# DicioBkUP.net
KiCad netlist of a schematic drawn in EAGLE
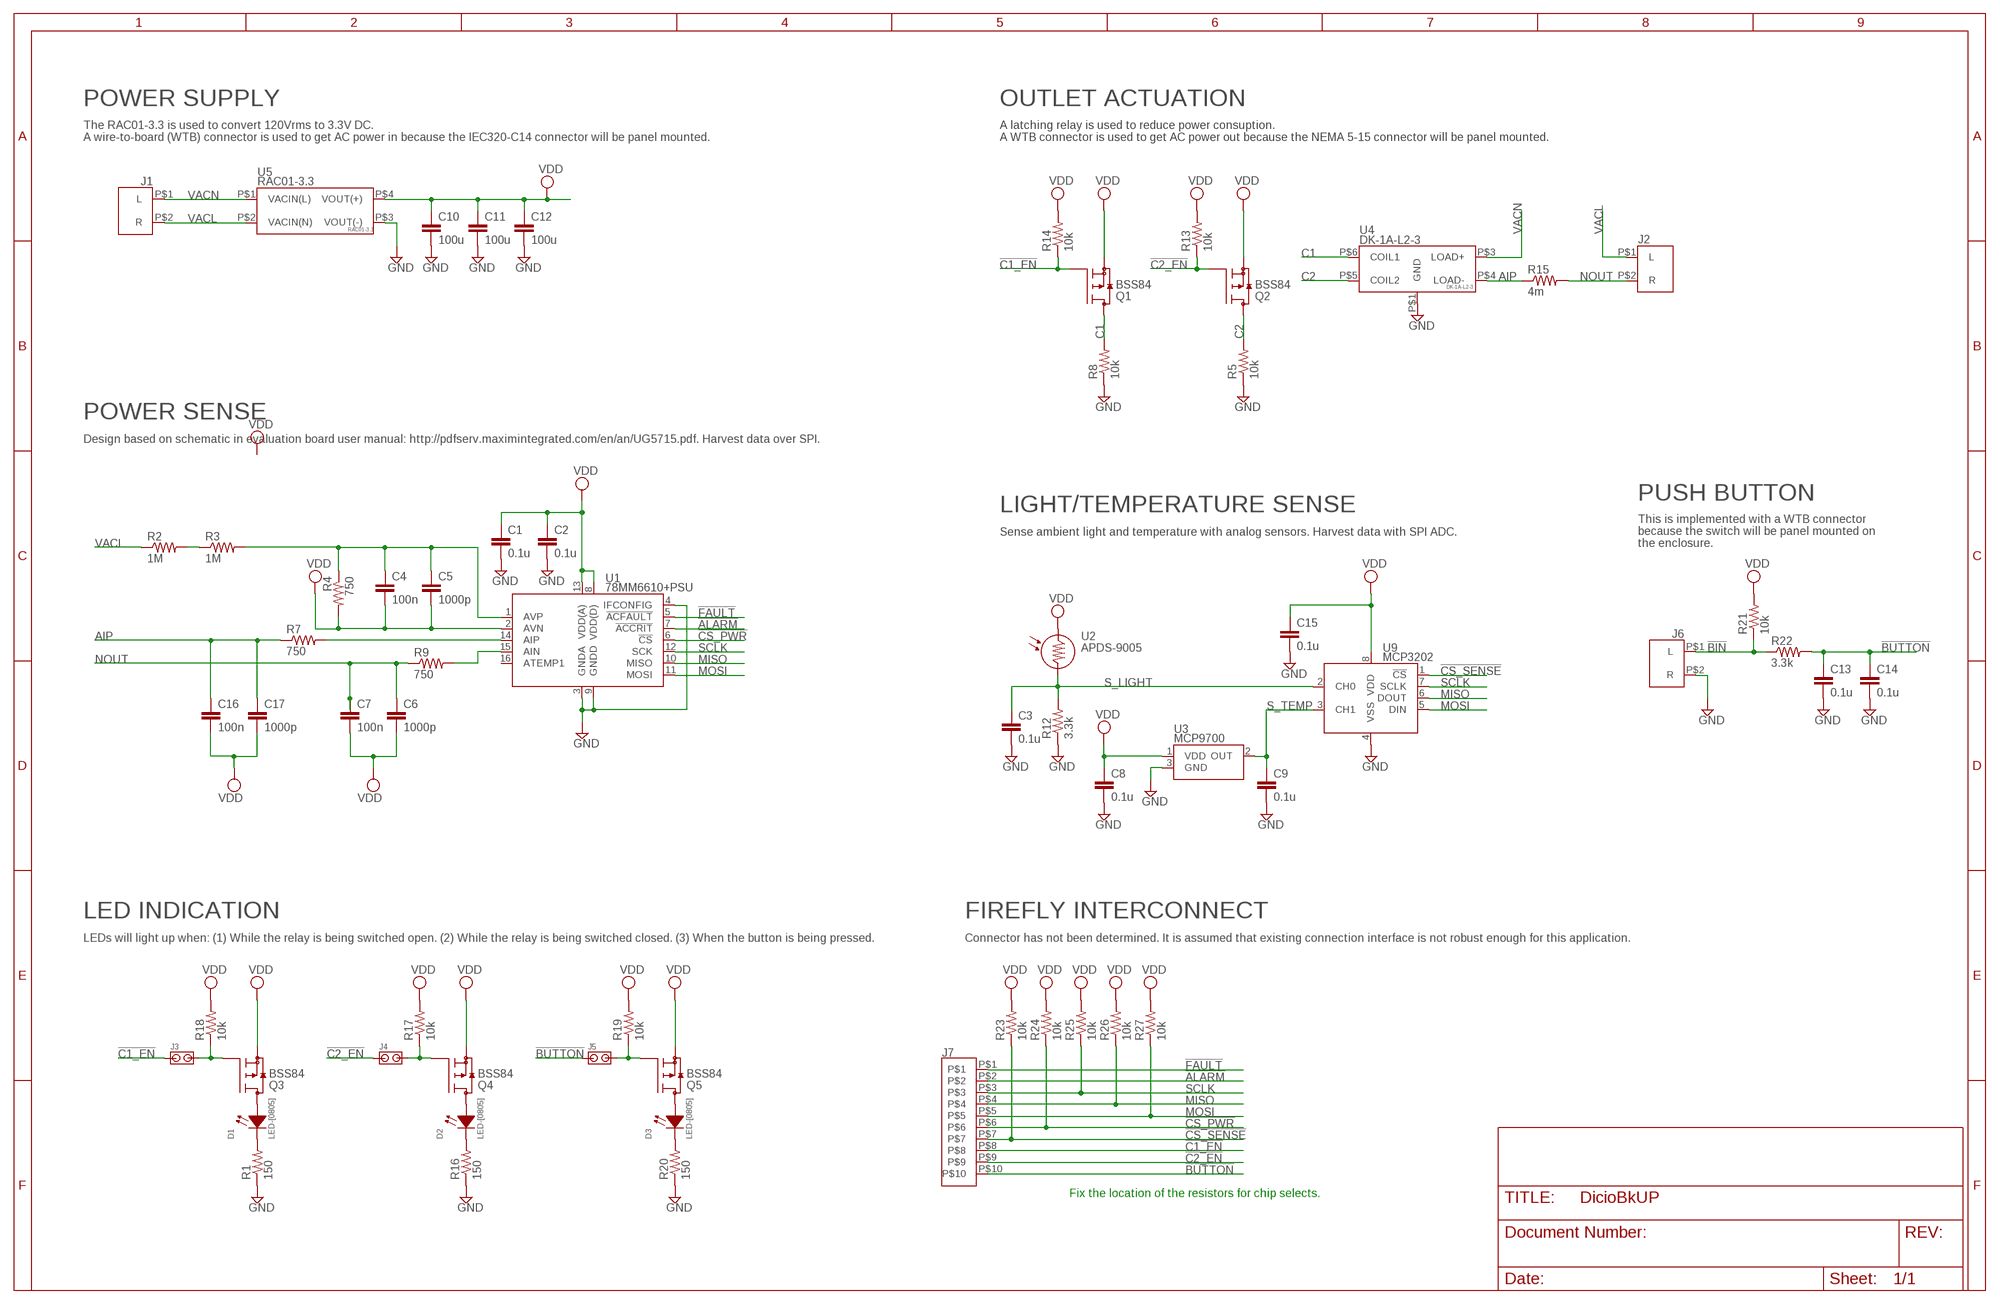
[diagram p0: schematic, sheet 1]

(export (version "E")
  (design (tool "Eeschema 10.0.6"))
  (components
    (comp (ref "C1")
      (value "0.1u")
      (footprint "eagle-import:C0805")
      (libsource (lib "eagle-import") (part "C-EUC0805"))
    )
    (comp (ref "C2")
      (value "0.1u")
      (footprint "eagle-import:C0805")
      (libsource (lib "eagle-import") (part "C-EUC0805"))
    )
    (comp (ref "C3")
      (value "0.1u")
      (footprint "eagle-import:C0805")
      (libsource (lib "eagle-import") (part "C-EUC0805"))
    )
    (comp (ref "C4")
      (value "100n")
      (footprint "eagle-import:C0805")
      (libsource (lib "eagle-import") (part "C-EUC0805"))
    )
    (comp (ref "C5")
      (value "1000p")
      (footprint "eagle-import:C0805")
      (libsource (lib "eagle-import") (part "C-EUC0805"))
    )
    (comp (ref "C6")
      (value "1000p")
      (footprint "eagle-import:C0805")
      (libsource (lib "eagle-import") (part "C-EUC0805"))
    )
    (comp (ref "C7")
      (value "100n")
      (footprint "eagle-import:C0805")
      (libsource (lib "eagle-import") (part "C-EUC0805"))
    )
    (comp (ref "C8")
      (value "0.1u")
      (footprint "eagle-import:C0805")
      (libsource (lib "eagle-import") (part "C-EUC0805"))
    )
    (comp (ref "C9")
      (value "0.1u")
      (footprint "eagle-import:C0805")
      (libsource (lib "eagle-import") (part "C-EUC0805"))
    )
    (comp (ref "C10")
      (value "100u")
      (footprint "eagle-import:C1206")
      (libsource (lib "eagle-import") (part "C-EUC1206"))
    )
    (comp (ref "C11")
      (value "100u")
      (footprint "eagle-import:C1206")
      (libsource (lib "eagle-import") (part "C-EUC1206"))
    )
    (comp (ref "C12")
      (value "100u")
      (footprint "eagle-import:C1206")
      (libsource (lib "eagle-import") (part "C-EUC1206"))
    )
    (comp (ref "C13")
      (value "0.1u")
      (footprint "eagle-import:C0805")
      (libsource (lib "eagle-import") (part "C-EUC0805"))
    )
    (comp (ref "C14")
      (value "0.1u")
      (footprint "eagle-import:C0805")
      (libsource (lib "eagle-import") (part "C-EUC0805"))
    )
    (comp (ref "C15")
      (value "0.1u")
      (footprint "eagle-import:C0805")
      (libsource (lib "eagle-import") (part "C-EUC0805"))
    )
    (comp (ref "C16")
      (value "100n")
      (footprint "eagle-import:C0805")
      (libsource (lib "eagle-import") (part "C-EUC0805"))
    )
    (comp (ref "C17")
      (value "1000p")
      (footprint "eagle-import:C0805")
      (libsource (lib "eagle-import") (part "C-EUC0805"))
    )
    (comp (ref "D1")
      (value "LED-[0805]")
      (footprint "eagle-import:L0805")
      (libsource (lib "eagle-import") (part "LED-[0805]"))
    )
    (comp (ref "D2")
      (value "LED-[0805]")
      (footprint "eagle-import:L0805")
      (libsource (lib "eagle-import") (part "LED-[0805]"))
    )
    (comp (ref "D3")
      (value "LED-[0805]")
      (footprint "eagle-import:L0805")
      (libsource (lib "eagle-import") (part "LED-[0805]"))
    )
    (comp (ref "J1")
      (value "WTB-2")
      (footprint "eagle-import:[TERM][2][0.2]")
      (libsource (lib "eagle-import") (part "WTB-2"))
    )
    (comp (ref "J2")
      (value "WTB-2")
      (footprint "eagle-import:[TERM][2][0.2]")
      (libsource (lib "eagle-import") (part "WTB-2"))
    )
    (comp (ref "J3")
      (value "JMP2")
      (footprint "eagle-import:JMP2")
      (libsource (lib "eagle-import") (part "JMP2"))
    )
    (comp (ref "J4")
      (value "JMP2")
      (footprint "eagle-import:JMP2")
      (libsource (lib "eagle-import") (part "JMP2"))
    )
    (comp (ref "J5")
      (value "JMP2")
      (footprint "eagle-import:JMP2")
      (libsource (lib "eagle-import") (part "JMP2"))
    )
    (comp (ref "J6")
      (value "WTB-2")
      (footprint "eagle-import:[TERM][2][0.2]")
      (libsource (lib "eagle-import") (part "WTB-2"))
    )
    (comp (ref "J7")
      (value "TERM10")
      (footprint "eagle-import:TERM10")
      (libsource (lib "eagle-import") (part "TERM10"))
    )
    (comp (ref "Q1")
      (value "BSS84")
      (footprint "eagle-import:SOT23")
      (libsource (lib "eagle-import") (part "BSS84"))
    )
    (comp (ref "Q2")
      (value "BSS84")
      (footprint "eagle-import:SOT23")
      (libsource (lib "eagle-import") (part "BSS84"))
    )
    (comp (ref "Q3")
      (value "BSS84")
      (footprint "eagle-import:SOT23")
      (libsource (lib "eagle-import") (part "BSS84"))
    )
    (comp (ref "Q4")
      (value "BSS84")
      (footprint "eagle-import:SOT23")
      (libsource (lib "eagle-import") (part "BSS84"))
    )
    (comp (ref "Q5")
      (value "BSS84")
      (footprint "eagle-import:SOT23")
      (libsource (lib "eagle-import") (part "BSS84"))
    )
    (comp (ref "R1")
      (value "150")
      (footprint "eagle-import:R0805")
      (libsource (lib "eagle-import") (part "R-US_R0805"))
    )
    (comp (ref "R2")
      (value "1M")
      (footprint "eagle-import:R0805")
      (libsource (lib "eagle-import") (part "R-US_R0805"))
    )
    (comp (ref "R3")
      (value "1M")
      (footprint "eagle-import:R0805")
      (libsource (lib "eagle-import") (part "R-US_R0805"))
    )
    (comp (ref "R4")
      (value "750")
      (footprint "eagle-import:R0805")
      (libsource (lib "eagle-import") (part "R-US_R0805"))
    )
    (comp (ref "R5")
      (value "10k")
      (footprint "eagle-import:R0805")
      (libsource (lib "eagle-import") (part "R-US_R0805"))
    )
    (comp (ref "R7")
      (value "750")
      (footprint "eagle-import:R0805")
      (libsource (lib "eagle-import") (part "R-US_R0805"))
    )
    (comp (ref "R8")
      (value "10k")
      (footprint "eagle-import:R0805")
      (libsource (lib "eagle-import") (part "R-US_R0805"))
    )
    (comp (ref "R9")
      (value "750")
      (footprint "eagle-import:R0805")
      (libsource (lib "eagle-import") (part "R-US_R0805"))
    )
    (comp (ref "R12")
      (value "3.3k")
      (footprint "eagle-import:R0805")
      (libsource (lib "eagle-import") (part "R-US_R0805"))
    )
    (comp (ref "R13")
      (value "10k")
      (footprint "eagle-import:R0805")
      (libsource (lib "eagle-import") (part "R-US_R0805"))
    )
    (comp (ref "R14")
      (value "10k")
      (footprint "eagle-import:R0805")
      (libsource (lib "eagle-import") (part "R-US_R0805"))
    )
    (comp (ref "R15")
      (value "4m")
      (footprint "eagle-import:R2512")
      (libsource (lib "eagle-import") (part "R-US_R2512"))
    )
    (comp (ref "R16")
      (value "150")
      (footprint "eagle-import:R0805")
      (libsource (lib "eagle-import") (part "R-US_R0805"))
    )
    (comp (ref "R17")
      (value "10k")
      (footprint "eagle-import:R0805")
      (libsource (lib "eagle-import") (part "R-US_R0805"))
    )
    (comp (ref "R18")
      (value "10k")
      (footprint "eagle-import:R0805")
      (libsource (lib "eagle-import") (part "R-US_R0805"))
    )
    (comp (ref "R19")
      (value "10k")
      (footprint "eagle-import:R0805")
      (libsource (lib "eagle-import") (part "R-US_R0805"))
    )
    (comp (ref "R20")
      (value "150")
      (footprint "eagle-import:R0805")
      (libsource (lib "eagle-import") (part "R-US_R0805"))
    )
    (comp (ref "R21")
      (value "10k")
      (footprint "eagle-import:R0805")
      (libsource (lib "eagle-import") (part "R-US_R0805"))
    )
    (comp (ref "R22")
      (value "3.3k")
      (footprint "eagle-import:R0805")
      (libsource (lib "eagle-import") (part "R-US_R0805"))
    )
    (comp (ref "R23")
      (value "10k")
      (footprint "eagle-import:R0805")
      (libsource (lib "eagle-import") (part "R-US_R0805"))
    )
    (comp (ref "R24")
      (value "10k")
      (footprint "eagle-import:R0805")
      (libsource (lib "eagle-import") (part "R-US_R0805"))
    )
    (comp (ref "R25")
      (value "10k")
      (footprint "eagle-import:R0805")
      (libsource (lib "eagle-import") (part "R-US_R0805"))
    )
    (comp (ref "R26")
      (value "10k")
      (footprint "eagle-import:R0805")
      (libsource (lib "eagle-import") (part "R-US_R0805"))
    )
    (comp (ref "R27")
      (value "10k")
      (footprint "eagle-import:R0805")
      (libsource (lib "eagle-import") (part "R-US_R0805"))
    )
    (comp (ref "U1")
      (value "78MM6610+PSU")
      (footprint "eagle-import:TSSOP16")
      (libsource (lib "eagle-import") (part "78MM6610+PSU"))
    )
    (comp (ref "U2")
      (value "APDS-9005")
      (footprint "eagle-import:APDS-9005")
      (libsource (lib "eagle-import") (part "APDS-9005"))
    )
    (comp (ref "U3")
      (value "MCP9700")
      (footprint "eagle-import:SOT23")
      (libsource (lib "eagle-import") (part "MCP9700"))
    )
    (comp (ref "U4")
      (value "DK-1A-L2-3")
      (footprint "eagle-import:DK-1A-L2-3")
      (libsource (lib "eagle-import") (part "DK-1A-L2-3"))
    )
    (comp (ref "U5")
      (value "RAC01-3.3")
      (footprint "eagle-import:RAC01-3.3")
      (libsource (lib "eagle-import") (part "RAC01-3.3"))
    )
    (comp (ref "U9")
      (value "MCP3202")
      (footprint "eagle-import:MSOP-8[MCP3202]")
      (libsource (lib "eagle-import") (part "MCP3202"))
    )
  )
  (nets
    (net (code "1") (name "/AIP") (class "Default")
      (node (ref "C16") (pin "1") (pinfunction "1_1") (pintype "passive"))
      (node (ref "C17") (pin "1") (pinfunction "1_1") (pintype "passive"))
      (node (ref "R15") (pin "1") (pinfunction "1_1") (pintype "passive"))
      (node (ref "R7") (pin "1") (pinfunction "1_1") (pintype "passive"))
      (node (ref "U4") (pin "P$4") (pinfunction "LOAD-_P$4") (pintype "bidirectional"))
    )
    (net (code "2") (name "/C1") (class "Default")
      (node (ref "Q1") (pin "3") (pinfunction "D_3") (pintype "bidirectional"))
      (node (ref "R8") (pin "2") (pinfunction "2_2") (pintype "passive"))
      (node (ref "U4") (pin "P$6") (pinfunction "COIL1_P$6") (pintype "bidirectional"))
    )
    (net (code "3") (name "/C2") (class "Default")
      (node (ref "Q2") (pin "3") (pinfunction "D_3") (pintype "bidirectional"))
      (node (ref "R5") (pin "2") (pinfunction "2_2") (pintype "passive"))
      (node (ref "U4") (pin "P$5") (pinfunction "COIL2_P$5") (pintype "bidirectional"))
    )
    (net (code "4") (name "/MISO") (class "Default")
      (node (ref "J7") (pin "P$4") (pinfunction "P$4_P$4") (pintype "bidirectional"))
      (node (ref "R26") (pin "1") (pinfunction "1_1") (pintype "passive"))
      (node (ref "U1") (pin "10") (pinfunction "MISO_10") (pintype "bidirectional"))
      (node (ref "U9") (pin "6") (pinfunction "DOUT_6") (pintype "bidirectional"))
    )
    (net (code "5") (name "/MOSI") (class "Default")
      (node (ref "J7") (pin "P$5") (pinfunction "P$5_P$5") (pintype "bidirectional"))
      (node (ref "R27") (pin "1") (pinfunction "1_1") (pintype "passive"))
      (node (ref "U1") (pin "11") (pinfunction "MOSI_11") (pintype "bidirectional"))
      (node (ref "U9") (pin "5") (pinfunction "DIN_5") (pintype "bidirectional"))
    )
    (net (code "6") (name "/NOUT") (class "Default")
      (node (ref "C6") (pin "1") (pinfunction "1_1") (pintype "passive"))
      (node (ref "C7") (pin "1") (pinfunction "1_1") (pintype "passive"))
      (node (ref "J2") (pin "P$2") (pinfunction "R_P$2") (pintype "bidirectional"))
      (node (ref "R15") (pin "2") (pinfunction "2_2") (pintype "passive"))
      (node (ref "R9") (pin "1") (pinfunction "1_1") (pintype "passive"))
    )
    (net (code "7") (name "/SCLK") (class "Default")
      (node (ref "J7") (pin "P$3") (pinfunction "P$3_P$3") (pintype "bidirectional"))
      (node (ref "R25") (pin "1") (pinfunction "1_1") (pintype "passive"))
      (node (ref "U1") (pin "12") (pinfunction "SCK_12") (pintype "bidirectional"))
      (node (ref "U9") (pin "7") (pinfunction "SCLK_7") (pintype "bidirectional"))
    )
    (net (code "8") (name "/S_LIGHT") (class "Default")
      (node (ref "C3") (pin "1") (pinfunction "1_1") (pintype "passive"))
      (node (ref "R12") (pin "2") (pinfunction "2_2") (pintype "passive"))
      (node (ref "U2") (pin "6") (pinfunction "ROUT_6") (pintype "bidirectional"))
      (node (ref "U9") (pin "2") (pinfunction "CH0_2") (pintype "bidirectional"))
    )
    (net (code "9") (name "/S_TEMP") (class "Default")
      (node (ref "C9") (pin "1") (pinfunction "1_1") (pintype "passive"))
      (node (ref "U3") (pin "2") (pinfunction "OUT_2") (pintype "bidirectional"))
      (node (ref "U9") (pin "3") (pinfunction "CH1_3") (pintype "bidirectional"))
    )
    (net (code "10") (name "/VACL") (class "Default")
      (node (ref "J1") (pin "P$2") (pinfunction "R_P$2") (pintype "bidirectional"))
      (node (ref "J2") (pin "P$1") (pinfunction "L_P$1") (pintype "bidirectional"))
      (node (ref "R2") (pin "1") (pinfunction "1_1") (pintype "passive"))
      (node (ref "U5") (pin "P$2") (pinfunction "VACIN(N)_P$2") (pintype "bidirectional"))
    )
    (net (code "11") (name "/VACN") (class "Default")
      (node (ref "J1") (pin "P$1") (pinfunction "L_P$1") (pintype "bidirectional"))
      (node (ref "U4") (pin "P$3") (pinfunction "LOAD+_P$3") (pintype "bidirectional"))
      (node (ref "U5") (pin "P$1") (pinfunction "VACIN(L)_P$1") (pintype "bidirectional"))
    )
    (net (code "12") (name "/~{ALARM}") (class "Default")
      (node (ref "J7") (pin "P$2") (pinfunction "P$2_P$2") (pintype "bidirectional"))
      (node (ref "U1") (pin "7") (pinfunction "~{ACCRIT}_7") (pintype "bidirectional"))
    )
    (net (code "13") (name "/~{BIN}") (class "Default")
      (node (ref "J6") (pin "P$1") (pinfunction "L_P$1") (pintype "bidirectional"))
      (node (ref "R21") (pin "1") (pinfunction "1_1") (pintype "passive"))
      (node (ref "R22") (pin "1") (pinfunction "1_1") (pintype "passive"))
    )
    (net (code "14") (name "/~{BUTTON}") (class "Default")
      (node (ref "C13") (pin "1") (pinfunction "1_1") (pintype "passive"))
      (node (ref "C14") (pin "1") (pinfunction "1_1") (pintype "passive"))
      (node (ref "J5") (pin "P$2") (pinfunction "P$2_P$2") (pintype "bidirectional"))
      (node (ref "J7") (pin "P$10") (pinfunction "P$10_P$10") (pintype "bidirectional"))
      (node (ref "R22") (pin "2") (pinfunction "2_2") (pintype "passive"))
    )
    (net (code "15") (name "/~{C1_EN}") (class "Default")
      (node (ref "J3") (pin "P$2") (pinfunction "P$2_P$2") (pintype "bidirectional"))
      (node (ref "J7") (pin "P$8") (pinfunction "P$8_P$8") (pintype "bidirectional"))
      (node (ref "Q1") (pin "1") (pinfunction "G_1") (pintype "bidirectional"))
      (node (ref "R14") (pin "1") (pinfunction "1_1") (pintype "passive"))
    )
    (net (code "16") (name "/~{C2_EN}") (class "Default")
      (node (ref "J4") (pin "P$2") (pinfunction "P$2_P$2") (pintype "bidirectional"))
      (node (ref "J7") (pin "P$9") (pinfunction "P$9_P$9") (pintype "bidirectional"))
      (node (ref "Q2") (pin "1") (pinfunction "G_1") (pintype "bidirectional"))
      (node (ref "R13") (pin "1") (pinfunction "1_1") (pintype "passive"))
    )
    (net (code "17") (name "/~{CS_PWR}") (class "Default")
      (node (ref "J7") (pin "P$6") (pinfunction "P$6_P$6") (pintype "bidirectional"))
      (node (ref "R24") (pin "1") (pinfunction "1_1") (pintype "passive"))
      (node (ref "U1") (pin "6") (pinfunction "~{CS}_6") (pintype "bidirectional"))
    )
    (net (code "18") (name "/~{CS_SENSE}") (class "Default")
      (node (ref "J7") (pin "P$7") (pinfunction "P$7_P$7") (pintype "bidirectional"))
      (node (ref "R23") (pin "1") (pinfunction "1_1") (pintype "passive"))
      (node (ref "U9") (pin "1") (pinfunction "~{CS}_1") (pintype "bidirectional"))
    )
    (net (code "19") (name "/~{FAULT}") (class "Default")
      (node (ref "J7") (pin "P$1") (pinfunction "P$1_P$1") (pintype "bidirectional"))
      (node (ref "U1") (pin "5") (pinfunction "~{ACFAULT}_5") (pintype "bidirectional"))
    )
    (net (code "20") (name "GND") (class "Default")
      (node (ref "C1") (pin "2") (pinfunction "2_2") (pintype "passive"))
      (node (ref "C10") (pin "2") (pinfunction "2_2") (pintype "passive"))
      (node (ref "C11") (pin "2") (pinfunction "2_2") (pintype "passive"))
      (node (ref "C12") (pin "2") (pinfunction "2_2") (pintype "passive"))
      (node (ref "C13") (pin "2") (pinfunction "2_2") (pintype "passive"))
      (node (ref "C14") (pin "2") (pinfunction "2_2") (pintype "passive"))
      (node (ref "C15") (pin "2") (pinfunction "2_2") (pintype "passive"))
      (node (ref "C2") (pin "2") (pinfunction "2_2") (pintype "passive"))
      (node (ref "C3") (pin "2") (pinfunction "2_2") (pintype "passive"))
      (node (ref "C8") (pin "2") (pinfunction "2_2") (pintype "passive"))
      (node (ref "C9") (pin "2") (pinfunction "2_2") (pintype "passive"))
      (node (ref "J6") (pin "P$2") (pinfunction "R_P$2") (pintype "bidirectional"))
      (node (ref "R1") (pin "1") (pinfunction "1_1") (pintype "passive"))
      (node (ref "R12") (pin "1") (pinfunction "1_1") (pintype "passive"))
      (node (ref "R16") (pin "1") (pinfunction "1_1") (pintype "passive"))
      (node (ref "R20") (pin "1") (pinfunction "1_1") (pintype "passive"))
      (node (ref "R5") (pin "1") (pinfunction "1_1") (pintype "passive"))
      (node (ref "R8") (pin "1") (pinfunction "1_1") (pintype "passive"))
      (node (ref "U1") (pin "3") (pinfunction "GNDA_3") (pintype "bidirectional"))
      (node (ref "U1") (pin "4") (pinfunction "IFCONFIG_4") (pintype "bidirectional"))
      (node (ref "U1") (pin "9") (pinfunction "GNDD_9") (pintype "bidirectional"))
      (node (ref "U3") (pin "3") (pinfunction "GND_3") (pintype "bidirectional"))
      (node (ref "U4") (pin "P$1") (pinfunction "GND_P$1") (pintype "bidirectional"))
      (node (ref "U5") (pin "P$3") (pinfunction "VOUT(-)_P$3") (pintype "bidirectional"))
      (node (ref "U9") (pin "4") (pinfunction "VSS_4") (pintype "bidirectional"))
    )
    (net (code "21") (name "Net-(D1-A)") (class "Default")
      (node (ref "D1") (pin "1") (pinfunction "A_1") (pintype "bidirectional"))
      (node (ref "Q3") (pin "3") (pinfunction "D_3") (pintype "bidirectional"))
    )
    (net (code "22") (name "Net-(D1-C)") (class "Default")
      (node (ref "D1") (pin "2") (pinfunction "C_2") (pintype "bidirectional"))
      (node (ref "R1") (pin "2") (pinfunction "2_2") (pintype "passive"))
    )
    (net (code "23") (name "Net-(D2-A)") (class "Default")
      (node (ref "D2") (pin "1") (pinfunction "A_1") (pintype "bidirectional"))
      (node (ref "Q4") (pin "3") (pinfunction "D_3") (pintype "bidirectional"))
    )
    (net (code "24") (name "Net-(D2-C)") (class "Default")
      (node (ref "D2") (pin "2") (pinfunction "C_2") (pintype "bidirectional"))
      (node (ref "R16") (pin "2") (pinfunction "2_2") (pintype "passive"))
    )
    (net (code "25") (name "Net-(D3-A)") (class "Default")
      (node (ref "D3") (pin "1") (pinfunction "A_1") (pintype "bidirectional"))
      (node (ref "Q5") (pin "3") (pinfunction "D_3") (pintype "bidirectional"))
    )
    (net (code "26") (name "Net-(D3-C)") (class "Default")
      (node (ref "D3") (pin "2") (pinfunction "C_2") (pintype "bidirectional"))
      (node (ref "R20") (pin "2") (pinfunction "2_2") (pintype "passive"))
    )
    (net (code "27") (name "Net-(J3-1)") (class "Default")
      (node (ref "J3") (pin "P$1") (pinfunction "1_P$1") (pintype "bidirectional"))
      (node (ref "Q3") (pin "1") (pinfunction "G_1") (pintype "bidirectional"))
      (node (ref "R18") (pin "1") (pinfunction "1_1") (pintype "passive"))
    )
    (net (code "28") (name "Net-(J4-1)") (class "Default")
      (node (ref "J4") (pin "P$1") (pinfunction "1_P$1") (pintype "bidirectional"))
      (node (ref "Q4") (pin "1") (pinfunction "G_1") (pintype "bidirectional"))
      (node (ref "R17") (pin "1") (pinfunction "1_1") (pintype "passive"))
    )
    (net (code "29") (name "Net-(J5-1)") (class "Default")
      (node (ref "J5") (pin "P$1") (pinfunction "1_P$1") (pintype "bidirectional"))
      (node (ref "Q5") (pin "1") (pinfunction "G_1") (pintype "bidirectional"))
      (node (ref "R19") (pin "1") (pinfunction "1_1") (pintype "passive"))
    )
    (net (code "30") (name "Net-(R2-Pad2)") (class "Default")
      (node (ref "R2") (pin "2") (pinfunction "2_2") (pintype "passive"))
      (node (ref "R3") (pin "1") (pinfunction "1_1") (pintype "passive"))
    )
    (net (code "31") (name "Net-(U1-AIN)") (class "Default")
      (node (ref "R9") (pin "2") (pinfunction "2_2") (pintype "passive"))
      (node (ref "U1") (pin "15") (pinfunction "AIN_15") (pintype "bidirectional"))
    )
    (net (code "32") (name "Net-(U1-AIP)") (class "Default")
      (node (ref "R7") (pin "2") (pinfunction "2_2") (pintype "passive"))
      (node (ref "U1") (pin "14") (pinfunction "AIP_14") (pintype "bidirectional"))
    )
    (net (code "33") (name "Net-(U1-AVP)") (class "Default")
      (node (ref "C4") (pin "1") (pinfunction "1_1") (pintype "passive"))
      (node (ref "C5") (pin "1") (pinfunction "1_1") (pintype "passive"))
      (node (ref "R3") (pin "2") (pinfunction "2_2") (pintype "passive"))
      (node (ref "R4") (pin "1") (pinfunction "1_1") (pintype "passive"))
      (node (ref "U1") (pin "1") (pinfunction "AVP_1") (pintype "bidirectional"))
    )
    (net (code "34") (name "VDD") (class "Default")
      (node (ref "C1") (pin "1") (pinfunction "1_1") (pintype "passive"))
      (node (ref "C10") (pin "1") (pinfunction "1_1") (pintype "passive"))
      (node (ref "C11") (pin "1") (pinfunction "1_1") (pintype "passive"))
      (node (ref "C12") (pin "1") (pinfunction "1_1") (pintype "passive"))
      (node (ref "C15") (pin "1") (pinfunction "1_1") (pintype "passive"))
      (node (ref "C16") (pin "2") (pinfunction "2_2") (pintype "passive"))
      (node (ref "C17") (pin "2") (pinfunction "2_2") (pintype "passive"))
      (node (ref "C2") (pin "1") (pinfunction "1_1") (pintype "passive"))
      (node (ref "C4") (pin "2") (pinfunction "2_2") (pintype "passive"))
      (node (ref "C5") (pin "2") (pinfunction "2_2") (pintype "passive"))
      (node (ref "C6") (pin "2") (pinfunction "2_2") (pintype "passive"))
      (node (ref "C7") (pin "2") (pinfunction "2_2") (pintype "passive"))
      (node (ref "C8") (pin "1") (pinfunction "1_1") (pintype "passive"))
      (node (ref "Q1") (pin "2") (pinfunction "S_2") (pintype "bidirectional"))
      (node (ref "Q2") (pin "2") (pinfunction "S_2") (pintype "bidirectional"))
      (node (ref "Q3") (pin "2") (pinfunction "S_2") (pintype "bidirectional"))
      (node (ref "Q4") (pin "2") (pinfunction "S_2") (pintype "bidirectional"))
      (node (ref "Q5") (pin "2") (pinfunction "S_2") (pintype "bidirectional"))
      (node (ref "R13") (pin "2") (pinfunction "2_2") (pintype "passive"))
      (node (ref "R14") (pin "2") (pinfunction "2_2") (pintype "passive"))
      (node (ref "R17") (pin "2") (pinfunction "2_2") (pintype "passive"))
      (node (ref "R18") (pin "2") (pinfunction "2_2") (pintype "passive"))
      (node (ref "R19") (pin "2") (pinfunction "2_2") (pintype "passive"))
      (node (ref "R21") (pin "2") (pinfunction "2_2") (pintype "passive"))
      (node (ref "R23") (pin "2") (pinfunction "2_2") (pintype "passive"))
      (node (ref "R24") (pin "2") (pinfunction "2_2") (pintype "passive"))
      (node (ref "R25") (pin "2") (pinfunction "2_2") (pintype "passive"))
      (node (ref "R26") (pin "2") (pinfunction "2_2") (pintype "passive"))
      (node (ref "R27") (pin "2") (pinfunction "2_2") (pintype "passive"))
      (node (ref "R4") (pin "2") (pinfunction "2_2") (pintype "passive"))
      (node (ref "U1") (pin "13") (pinfunction "VDD(A)_13") (pintype "bidirectional"))
      (node (ref "U1") (pin "2") (pinfunction "AVN_2") (pintype "bidirectional"))
      (node (ref "U1") (pin "8") (pinfunction "VDD(D)_8") (pintype "bidirectional"))
      (node (ref "U2") (pin "1") (pinfunction "VDD_1") (pintype "bidirectional"))
      (node (ref "U3") (pin "1") (pinfunction "VDD_1") (pintype "bidirectional"))
      (node (ref "U5") (pin "P$4") (pinfunction "VOUT(+)_P$4") (pintype "bidirectional"))
      (node (ref "U9") (pin "8") (pinfunction "VDD_8") (pintype "bidirectional"))
    )
    (net (code "35") (name "unconnected-(U1-ATEMP1-Pad16)") (class "Default")
      (node (ref "U1") (pin "16") (pinfunction "ATEMP1_16") (pintype "bidirectional"))
    )
    (net (code "36") (name "unconnected-(U2-NC1-Pad2)") (class "Default")
      (node (ref "U2") (pin "2") (pinfunction "NC1_2") (pintype "bidirectional"))
    )
    (net (code "37") (name "unconnected-(U2-NC2-Pad3)") (class "Default")
      (node (ref "U2") (pin "3") (pinfunction "NC2_3") (pintype "bidirectional"))
    )
    (net (code "38") (name "unconnected-(U2-NC3-Pad4)") (class "Default")
      (node (ref "U2") (pin "4") (pinfunction "NC3_4") (pintype "bidirectional"))
    )
    (net (code "39") (name "unconnected-(U2-NC4-Pad5)") (class "Default")
      (node (ref "U2") (pin "5") (pinfunction "NC4_5") (pintype "bidirectional"))
    )
  )
)
